# MiniCurrentAmp.net
KiCad netlist of a schematic drawn in EAGLE
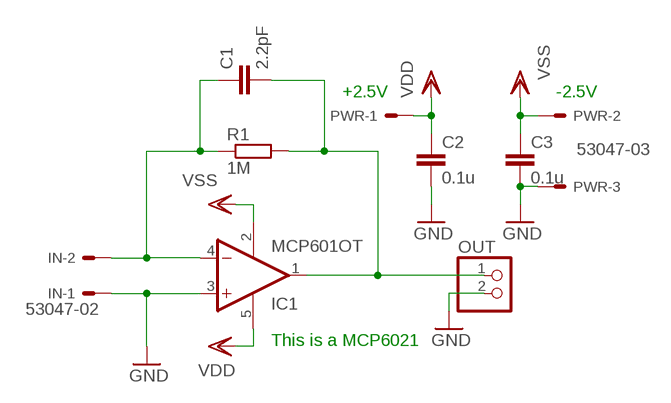
[diagram p0: schematic, sheet 1]

(export (version "E")
  (design (tool "Eeschema 10.0.6"))
  (components
    (comp (ref "C1")
      (value "2.2pF")
      (footprint "eagle-import:C0805")
      (libsource (lib "eagle-import") (part "C-EUC0805"))
    )
    (comp (ref "C2")
      (value "0.1u")
      (footprint "eagle-import:C0805")
      (libsource (lib "eagle-import") (part "C-EUC0805"))
    )
    (comp (ref "C3")
      (value "0.1u")
      (footprint "eagle-import:C0805")
      (libsource (lib "eagle-import") (part "C-EUC0805"))
    )
    (comp (ref "IC1")
      (value "MCP601OT")
      (footprint "eagle-import:SOT23-5")
      (libsource (lib "eagle-import") (part "MCP601OT"))
    )
    (comp (ref "IN")
      (value "53047-02")
      (footprint "eagle-import:53047-02")
      (fields (field (name "MF") "MOLEX") (field (name "MPN") "53047-0210"))
      (libsource (lib "eagle-import") (part "53?-02047"))
    )
    (comp (ref "OUT")
      (value "PINHD-1X2")
      (footprint "eagle-import:1X02")
      (libsource (lib "eagle-import") (part "PINHD-1X2"))
    )
    (comp (ref "PWR")
      (value "53047-03")
      (footprint "eagle-import:53047-03")
      (fields (field (name "MF") "MOLEX") (field (name "MPN") "530470310"))
      (libsource (lib "eagle-import") (part "53?-03047"))
    )
    (comp (ref "R1")
      (value "1M")
      (footprint "eagle-import:R0805")
      (libsource (lib "eagle-import") (part "R-EU_R0805"))
    )
  )
  (nets
    (net (code "1") (name "GND") (class "Default")
      (node (ref "C2") (pin "2") (pinfunction "2_2") (pintype "passive"))
      (node (ref "C3") (pin "2") (pinfunction "2_2") (pintype "passive"))
      (node (ref "IC1") (pin "3") (pinfunction "+IN_3") (pintype "input"))
      (node (ref "IN") (pin "1") (pinfunction "S_1") (pintype "passive"))
      (node (ref "OUT") (pin "2") (pinfunction "2_2") (pintype "passive"))
      (node (ref "PWR") (pin "3") (pinfunction "S_3") (pintype "passive"))
    )
    (net (code "2") (name "Net-(IC1--IN)") (class "Default")
      (node (ref "C1") (pin "1") (pinfunction "1_1") (pintype "passive"))
      (node (ref "IC1") (pin "4") (pinfunction "-IN_4") (pintype "input"))
      (node (ref "IN") (pin "2") (pinfunction "S_2") (pintype "passive"))
      (node (ref "R1") (pin "1") (pinfunction "1_1") (pintype "passive"))
    )
    (net (code "3") (name "Net-(IC1-OUT)") (class "Default")
      (node (ref "C1") (pin "2") (pinfunction "2_2") (pintype "passive"))
      (node (ref "IC1") (pin "1") (pinfunction "OUT_1") (pintype "output"))
      (node (ref "OUT") (pin "1") (pinfunction "1_1") (pintype "passive"))
      (node (ref "R1") (pin "2") (pinfunction "2_2") (pintype "passive"))
    )
    (net (code "4") (name "VDD") (class "Default")
      (node (ref "C2") (pin "1") (pinfunction "1_1") (pintype "passive"))
      (node (ref "IC1") (pin "5") (pinfunction "V+_5") (pintype "power_in"))
      (node (ref "PWR") (pin "1") (pinfunction "S_1") (pintype "passive"))
    )
    (net (code "5") (name "VSS") (class "Default")
      (node (ref "C3") (pin "1") (pinfunction "1_1") (pintype "passive"))
      (node (ref "IC1") (pin "2") (pinfunction "V-_2") (pintype "power_in"))
      (node (ref "PWR") (pin "2") (pinfunction "S_2") (pintype "passive"))
    )
  )
)
